# PLIS_POWER.net
KiCad netlist of a schematic drawn in Altium Designer
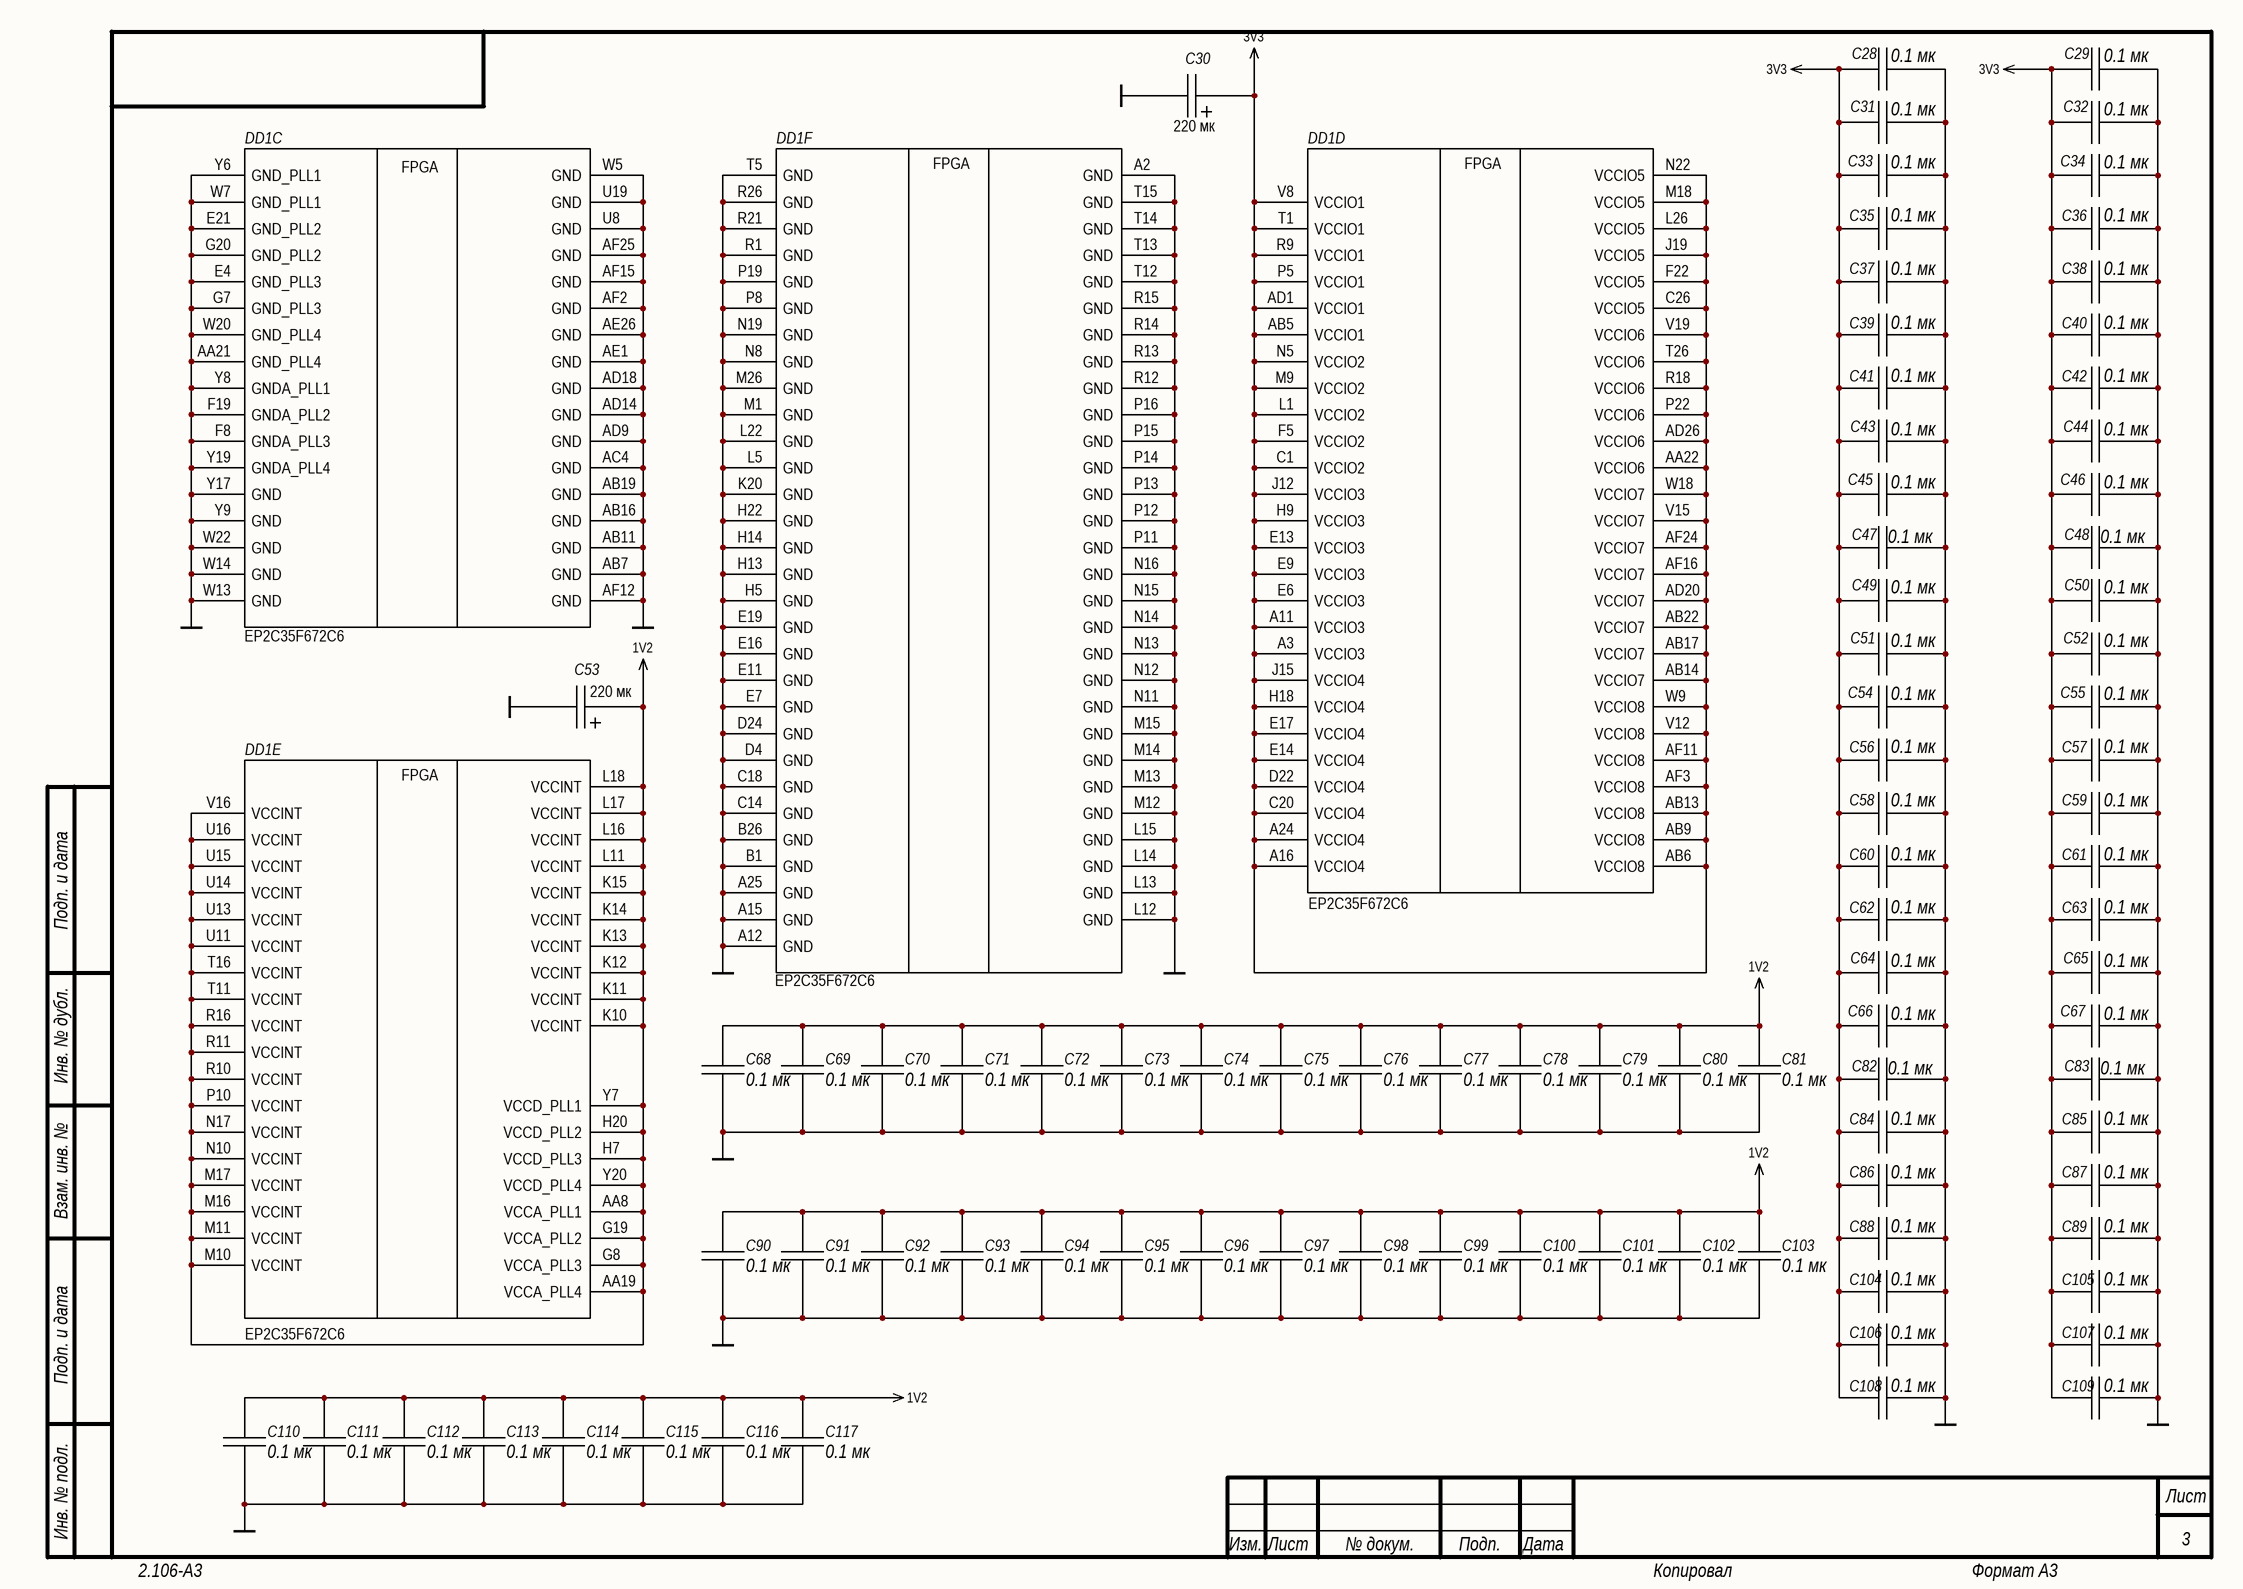
[diagram p0: PLIS_POWER.SchDoc]

(export (version "E")
  (design (tool "Eeschema 10.0.6"))
  (components
    (comp (ref "C28") (value "0.1 мк") (libsource (lib "Schlib1") (part "C")))
    (comp (ref "C29") (value "0.1 мк") (libsource (lib "Schlib1") (part "C")))
    (comp (ref "C30") (value "~") (libsource (lib "Schlib1") (part "C_POL")))
    (comp (ref "C31") (value "0.1 мк") (libsource (lib "Schlib1") (part "C")))
    (comp (ref "C32") (value "0.1 мк") (libsource (lib "Schlib1") (part "C")))
    (comp (ref "C33") (value "0.1 мк") (libsource (lib "Schlib1") (part "C")))
    (comp (ref "C34") (value "0.1 мк") (libsource (lib "Schlib1") (part "C")))
    (comp (ref "C35") (value "0.1 мк") (libsource (lib "Schlib1") (part "C")))
    (comp (ref "C36") (value "0.1 мк") (libsource (lib "Schlib1") (part "C")))
    (comp (ref "C37") (value "0.1 мк") (libsource (lib "Schlib1") (part "C")))
    (comp (ref "C38") (value "0.1 мк") (libsource (lib "Schlib1") (part "C")))
    (comp (ref "C39") (value "0.1 мк") (libsource (lib "Schlib1") (part "C")))
    (comp (ref "C40") (value "0.1 мк") (libsource (lib "Schlib1") (part "C")))
    (comp (ref "C41") (value "0.1 мк") (libsource (lib "Schlib1") (part "C")))
    (comp (ref "C42") (value "0.1 мк") (libsource (lib "Schlib1") (part "C")))
    (comp (ref "C43") (value "0.1 мк") (libsource (lib "Schlib1") (part "C")))
    (comp (ref "C44") (value "0.1 мк") (libsource (lib "Schlib1") (part "C")))
    (comp (ref "C45") (value "0.1 мк") (libsource (lib "Schlib1") (part "C")))
    (comp (ref "C46") (value "0.1 мк") (libsource (lib "Schlib1") (part "C")))
    (comp (ref "C47") (value "0.1 мк") (libsource (lib "Schlib1") (part "C")))
    (comp (ref "C48") (value "0.1 мк") (libsource (lib "Schlib1") (part "C")))
    (comp (ref "C49") (value "0.1 мк") (libsource (lib "Schlib1") (part "C")))
    (comp (ref "C50") (value "0.1 мк") (libsource (lib "Schlib1") (part "C")))
    (comp (ref "C51") (value "0.1 мк") (libsource (lib "Schlib1") (part "C")))
    (comp (ref "C52") (value "0.1 мк") (libsource (lib "Schlib1") (part "C")))
    (comp (ref "C53") (value "~") (libsource (lib "Schlib1") (part "C_POL")))
    (comp (ref "C54") (value "0.1 мк") (libsource (lib "Schlib1") (part "C")))
    (comp (ref "C55") (value "0.1 мк") (libsource (lib "Schlib1") (part "C")))
    (comp (ref "C56") (value "0.1 мк") (libsource (lib "Schlib1") (part "C")))
    (comp (ref "C57") (value "0.1 мк") (libsource (lib "Schlib1") (part "C")))
    (comp (ref "C58") (value "0.1 мк") (libsource (lib "Schlib1") (part "C")))
    (comp (ref "C59") (value "0.1 мк") (libsource (lib "Schlib1") (part "C")))
    (comp (ref "C60") (value "0.1 мк") (libsource (lib "Schlib1") (part "C")))
    (comp (ref "C61") (value "0.1 мк") (libsource (lib "Schlib1") (part "C")))
    (comp (ref "C62") (value "0.1 мк") (libsource (lib "Schlib1") (part "C")))
    (comp (ref "C63") (value "0.1 мк") (libsource (lib "Schlib1") (part "C")))
    (comp (ref "C64") (value "0.1 мк") (libsource (lib "Schlib1") (part "C")))
    (comp (ref "C65") (value "0.1 мк") (libsource (lib "Schlib1") (part "C")))
    (comp (ref "C66") (value "0.1 мк") (libsource (lib "Schlib1") (part "C")))
    (comp (ref "C67") (value "0.1 мк") (libsource (lib "Schlib1") (part "C")))
    (comp (ref "C68") (value "0.1 мк") (libsource (lib "Schlib1") (part "C")))
    (comp (ref "C69") (value "0.1 мк") (libsource (lib "Schlib1") (part "C")))
    (comp (ref "C70") (value "0.1 мк") (libsource (lib "Schlib1") (part "C")))
    (comp (ref "C71") (value "0.1 мк") (libsource (lib "Schlib1") (part "C")))
    (comp (ref "C72") (value "0.1 мк") (libsource (lib "Schlib1") (part "C")))
    (comp (ref "C73") (value "0.1 мк") (libsource (lib "Schlib1") (part "C")))
    (comp (ref "C74") (value "0.1 мк") (libsource (lib "Schlib1") (part "C")))
    (comp (ref "C75") (value "0.1 мк") (libsource (lib "Schlib1") (part "C")))
    (comp (ref "C76") (value "0.1 мк") (libsource (lib "Schlib1") (part "C")))
    (comp (ref "C77") (value "0.1 мк") (libsource (lib "Schlib1") (part "C")))
    (comp (ref "C78") (value "0.1 мк") (libsource (lib "Schlib1") (part "C")))
    (comp (ref "C79") (value "0.1 мк") (libsource (lib "Schlib1") (part "C")))
    (comp (ref "C80") (value "0.1 мк") (libsource (lib "Schlib1") (part "C")))
    (comp (ref "C81") (value "0.1 мк") (libsource (lib "Schlib1") (part "C")))
    (comp (ref "C82") (value "0.1 мк") (libsource (lib "Schlib1") (part "C")))
    (comp (ref "C83") (value "0.1 мк") (libsource (lib "Schlib1") (part "C")))
    (comp (ref "C84") (value "0.1 мк") (libsource (lib "Schlib1") (part "C")))
    (comp (ref "C85") (value "0.1 мк") (libsource (lib "Schlib1") (part "C")))
    (comp (ref "C86") (value "0.1 мк") (libsource (lib "Schlib1") (part "C")))
    (comp (ref "C87") (value "0.1 мк") (libsource (lib "Schlib1") (part "C")))
    (comp (ref "C88") (value "0.1 мк") (libsource (lib "Schlib1") (part "C")))
    (comp (ref "C89") (value "0.1 мк") (libsource (lib "Schlib1") (part "C")))
    (comp (ref "C90") (value "0.1 мк") (libsource (lib "Schlib1") (part "C")))
    (comp (ref "C91") (value "0.1 мк") (libsource (lib "Schlib1") (part "C")))
    (comp (ref "C92") (value "0.1 мк") (libsource (lib "Schlib1") (part "C")))
    (comp (ref "C93") (value "0.1 мк") (libsource (lib "Schlib1") (part "C")))
    (comp (ref "C94") (value "0.1 мк") (libsource (lib "Schlib1") (part "C")))
    (comp (ref "C95") (value "0.1 мк") (libsource (lib "Schlib1") (part "C")))
    (comp (ref "C96") (value "0.1 мк") (libsource (lib "Schlib1") (part "C")))
    (comp (ref "C97") (value "0.1 мк") (libsource (lib "Schlib1") (part "C")))
    (comp (ref "C98") (value "0.1 мк") (libsource (lib "Schlib1") (part "C")))
    (comp (ref "C99") (value "0.1 мк") (libsource (lib "Schlib1") (part "C")))
    (comp (ref "C100") (value "0.1 мк") (libsource (lib "Schlib1") (part "C")))
    (comp (ref "C101") (value "0.1 мк") (libsource (lib "Schlib1") (part "C")))
    (comp (ref "C102") (value "0.1 мк") (libsource (lib "Schlib1") (part "C")))
    (comp (ref "C103") (value "0.1 мк") (libsource (lib "Schlib1") (part "C")))
    (comp (ref "C104") (value "0.1 мк") (libsource (lib "Schlib1") (part "C")))
    (comp (ref "C105") (value "0.1 мк") (libsource (lib "Schlib1") (part "C")))
    (comp (ref "C106") (value "0.1 мк") (libsource (lib "Schlib1") (part "C")))
    (comp (ref "C107") (value "0.1 мк") (libsource (lib "Schlib1") (part "C")))
    (comp (ref "C108") (value "0.1 мк") (libsource (lib "Schlib1") (part "C")))
    (comp (ref "C109") (value "0.1 мк") (libsource (lib "Schlib1") (part "C")))
    (comp (ref "C110") (value "0.1 мк") (libsource (lib "Schlib1") (part "C")))
    (comp (ref "C111") (value "0.1 мк") (libsource (lib "Schlib1") (part "C")))
    (comp (ref "C112") (value "0.1 мк") (libsource (lib "Schlib1") (part "C")))
    (comp (ref "C113") (value "0.1 мк") (libsource (lib "Schlib1") (part "C")))
    (comp (ref "C114") (value "0.1 мк") (libsource (lib "Schlib1") (part "C")))
    (comp (ref "C115") (value "0.1 мк") (libsource (lib "Schlib1") (part "C")))
    (comp (ref "C116") (value "0.1 мк") (libsource (lib "Schlib1") (part "C")))
    (comp (ref "C117") (value "0.1 мк") (libsource (lib "Schlib1") (part "C")))
    (comp (ref "DD1") (value "EP2C35F672C6") (libsource (lib "Schlib1") (part "PLIS")))
  )
  (nets
    (net (code "1") (name "1V2") (class "Default")
      (node (ref "C100") (pin "1") (pintype "passive"))
      (node (ref "C101") (pin "1") (pintype "passive"))
      (node (ref "C102") (pin "1") (pintype "passive"))
      (node (ref "C103") (pin "1") (pintype "passive"))
      (node (ref "C110") (pin "1") (pintype "passive"))
      (node (ref "C111") (pin "1") (pintype "passive"))
      (node (ref "C112") (pin "1") (pintype "passive"))
      (node (ref "C113") (pin "1") (pintype "passive"))
      (node (ref "C114") (pin "1") (pintype "passive"))
      (node (ref "C115") (pin "1") (pintype "passive"))
      (node (ref "C116") (pin "1") (pintype "passive"))
      (node (ref "C117") (pin "1") (pintype "passive"))
      (node (ref "C53") (pin "2") (pintype "passive"))
      (node (ref "C68") (pin "1") (pintype "passive"))
      (node (ref "C69") (pin "1") (pintype "passive"))
      (node (ref "C70") (pin "1") (pintype "passive"))
      (node (ref "C71") (pin "1") (pintype "passive"))
      (node (ref "C72") (pin "1") (pintype "passive"))
      (node (ref "C73") (pin "1") (pintype "passive"))
      (node (ref "C74") (pin "1") (pintype "passive"))
      (node (ref "C75") (pin "1") (pintype "passive"))
      (node (ref "C76") (pin "1") (pintype "passive"))
      (node (ref "C77") (pin "1") (pintype "passive"))
      (node (ref "C78") (pin "1") (pintype "passive"))
      (node (ref "C79") (pin "1") (pintype "passive"))
      (node (ref "C80") (pin "1") (pintype "passive"))
      (node (ref "C81") (pin "1") (pintype "passive"))
      (node (ref "C90") (pin "1") (pintype "passive"))
      (node (ref "C91") (pin "1") (pintype "passive"))
      (node (ref "C92") (pin "1") (pintype "passive"))
      (node (ref "C93") (pin "1") (pintype "passive"))
      (node (ref "C94") (pin "1") (pintype "passive"))
      (node (ref "C95") (pin "1") (pintype "passive"))
      (node (ref "C96") (pin "1") (pintype "passive"))
      (node (ref "C97") (pin "1") (pintype "passive"))
      (node (ref "C98") (pin "1") (pintype "passive"))
      (node (ref "C99") (pin "1") (pintype "passive"))
      (node (ref "DD1") (pin "AA19") (pinfunction "VCCA_PLL4_AA19") (pintype "passive"))
      (node (ref "DD1") (pin "AA8") (pinfunction "VCCA_PLL1_AA8") (pintype "passive"))
      (node (ref "DD1") (pin "G19") (pinfunction "VCCA_PLL2_G19") (pintype "passive"))
      (node (ref "DD1") (pin "G8") (pinfunction "VCCA_PLL3_G8") (pintype "passive"))
      (node (ref "DD1") (pin "H20") (pinfunction "VCCD_PLL2_H20") (pintype "passive"))
      (node (ref "DD1") (pin "H7") (pinfunction "VCCD_PLL3_H7") (pintype "passive"))
      (node (ref "DD1") (pin "K10") (pinfunction "VCCINT_K10") (pintype "passive"))
      (node (ref "DD1") (pin "K11") (pinfunction "VCCINT_K11") (pintype "passive"))
      (node (ref "DD1") (pin "K12") (pinfunction "VCCINT_K12") (pintype "passive"))
      (node (ref "DD1") (pin "K13") (pinfunction "VCCINT_K13") (pintype "passive"))
      (node (ref "DD1") (pin "K14") (pinfunction "VCCINT_K14") (pintype "passive"))
      (node (ref "DD1") (pin "K15") (pinfunction "VCCINT_K15") (pintype "passive"))
      (node (ref "DD1") (pin "L11") (pinfunction "VCCINT_L11") (pintype "passive"))
      (node (ref "DD1") (pin "L16") (pinfunction "VCCINT_L16") (pintype "passive"))
      (node (ref "DD1") (pin "L17") (pinfunction "VCCINT_L17") (pintype "passive"))
      (node (ref "DD1") (pin "L18") (pinfunction "VCCINT_L18") (pintype "passive"))
      (node (ref "DD1") (pin "M10") (pinfunction "VCCINT_M10") (pintype "passive"))
      (node (ref "DD1") (pin "M11") (pinfunction "VCCINT_M11") (pintype "passive"))
      (node (ref "DD1") (pin "M16") (pinfunction "VCCINT_M16") (pintype "passive"))
      (node (ref "DD1") (pin "M17") (pinfunction "VCCINT_M17") (pintype "passive"))
      (node (ref "DD1") (pin "N10") (pinfunction "VCCINT_N10") (pintype "passive"))
      (node (ref "DD1") (pin "N17") (pinfunction "VCCINT_N17") (pintype "passive"))
      (node (ref "DD1") (pin "P10") (pinfunction "VCCINT_P10") (pintype "passive"))
      (node (ref "DD1") (pin "R10") (pinfunction "VCCINT_R10") (pintype "passive"))
      (node (ref "DD1") (pin "R11") (pinfunction "VCCINT_R11") (pintype "passive"))
      (node (ref "DD1") (pin "R16") (pinfunction "VCCINT_R16") (pintype "passive"))
      (node (ref "DD1") (pin "T11") (pinfunction "VCCINT_T11") (pintype "passive"))
      (node (ref "DD1") (pin "T16") (pinfunction "VCCINT_T16") (pintype "passive"))
      (node (ref "DD1") (pin "U11") (pinfunction "VCCINT_U11") (pintype "passive"))
      (node (ref "DD1") (pin "U13") (pinfunction "VCCINT_U13") (pintype "passive"))
      (node (ref "DD1") (pin "U14") (pinfunction "VCCINT_U14") (pintype "passive"))
      (node (ref "DD1") (pin "U15") (pinfunction "VCCINT_U15") (pintype "passive"))
      (node (ref "DD1") (pin "U16") (pinfunction "VCCINT_U16") (pintype "passive"))
      (node (ref "DD1") (pin "V16") (pinfunction "VCCINT_V16") (pintype "passive"))
      (node (ref "DD1") (pin "Y20") (pinfunction "VCCD_PLL4_Y20") (pintype "passive"))
      (node (ref "DD1") (pin "Y7") (pinfunction "VCCD_PLL1_Y7") (pintype "passive"))
    )
    (net (code "2") (name "3V3") (class "Default")
      (node (ref "C104") (pin "1") (pintype "passive"))
      (node (ref "C105") (pin "1") (pintype "passive"))
      (node (ref "C106") (pin "1") (pintype "passive"))
      (node (ref "C107") (pin "1") (pintype "passive"))
      (node (ref "C108") (pin "1") (pintype "passive"))
      (node (ref "C109") (pin "1") (pintype "passive"))
      (node (ref "C28") (pin "1") (pintype "passive"))
      (node (ref "C29") (pin "1") (pintype "passive"))
      (node (ref "C30") (pin "2") (pintype "passive"))
      (node (ref "C31") (pin "1") (pintype "passive"))
      (node (ref "C32") (pin "1") (pintype "passive"))
      (node (ref "C33") (pin "1") (pintype "passive"))
      (node (ref "C34") (pin "1") (pintype "passive"))
      (node (ref "C35") (pin "1") (pintype "passive"))
      (node (ref "C36") (pin "1") (pintype "passive"))
      (node (ref "C37") (pin "1") (pintype "passive"))
      (node (ref "C38") (pin "1") (pintype "passive"))
      (node (ref "C39") (pin "1") (pintype "passive"))
      (node (ref "C40") (pin "1") (pintype "passive"))
      (node (ref "C41") (pin "1") (pintype "passive"))
      (node (ref "C42") (pin "1") (pintype "passive"))
      (node (ref "C43") (pin "1") (pintype "passive"))
      (node (ref "C44") (pin "1") (pintype "passive"))
      (node (ref "C45") (pin "1") (pintype "passive"))
      (node (ref "C46") (pin "1") (pintype "passive"))
      (node (ref "C47") (pin "1") (pintype "passive"))
      (node (ref "C48") (pin "1") (pintype "passive"))
      (node (ref "C49") (pin "1") (pintype "passive"))
      (node (ref "C50") (pin "1") (pintype "passive"))
      (node (ref "C51") (pin "1") (pintype "passive"))
      (node (ref "C52") (pin "1") (pintype "passive"))
      (node (ref "C54") (pin "1") (pintype "passive"))
      (node (ref "C55") (pin "1") (pintype "passive"))
      (node (ref "C56") (pin "1") (pintype "passive"))
      (node (ref "C57") (pin "1") (pintype "passive"))
      (node (ref "C58") (pin "1") (pintype "passive"))
      (node (ref "C59") (pin "1") (pintype "passive"))
      (node (ref "C60") (pin "1") (pintype "passive"))
      (node (ref "C61") (pin "1") (pintype "passive"))
      (node (ref "C62") (pin "1") (pintype "passive"))
      (node (ref "C63") (pin "1") (pintype "passive"))
      (node (ref "C64") (pin "1") (pintype "passive"))
      (node (ref "C65") (pin "1") (pintype "passive"))
      (node (ref "C66") (pin "1") (pintype "passive"))
      (node (ref "C67") (pin "1") (pintype "passive"))
      (node (ref "C82") (pin "1") (pintype "passive"))
      (node (ref "C83") (pin "1") (pintype "passive"))
      (node (ref "C84") (pin "1") (pintype "passive"))
      (node (ref "C85") (pin "1") (pintype "passive"))
      (node (ref "C86") (pin "1") (pintype "passive"))
      (node (ref "C87") (pin "1") (pintype "passive"))
      (node (ref "C88") (pin "1") (pintype "passive"))
      (node (ref "C89") (pin "1") (pintype "passive"))
      (node (ref "DD1") (pin "A11") (pinfunction "VCCIO3_A11") (pintype "passive"))
      (node (ref "DD1") (pin "A16") (pinfunction "VCCIO4_A16") (pintype "passive"))
      (node (ref "DD1") (pin "A24") (pinfunction "VCCIO4_A24") (pintype "passive"))
      (node (ref "DD1") (pin "A3") (pinfunction "VCCIO3_A3") (pintype "passive"))
      (node (ref "DD1") (pin "AA22") (pinfunction "VCCIO6_AA22") (pintype "passive"))
      (node (ref "DD1") (pin "AB13") (pinfunction "VCCIO8_AB13") (pintype "passive"))
      (node (ref "DD1") (pin "AB14") (pinfunction "VCCIO7_AB14") (pintype "passive"))
      (node (ref "DD1") (pin "AB17") (pinfunction "VCCIO7_AB17") (pintype "passive"))
      (node (ref "DD1") (pin "AB22") (pinfunction "VCCIO7_AB22") (pintype "passive"))
      (node (ref "DD1") (pin "AB5") (pinfunction "VCCIO1_AB5") (pintype "passive"))
      (node (ref "DD1") (pin "AB6") (pinfunction "VCCIO8_AB6") (pintype "passive"))
      (node (ref "DD1") (pin "AB9") (pinfunction "VCCIO8_AB9") (pintype "passive"))
      (node (ref "DD1") (pin "AD1") (pinfunction "VCCIO1_AD1") (pintype "passive"))
      (node (ref "DD1") (pin "AD20") (pinfunction "VCCIO7_AD20") (pintype "passive"))
      (node (ref "DD1") (pin "AD26") (pinfunction "VCCIO6_AD26") (pintype "passive"))
      (node (ref "DD1") (pin "AF11") (pinfunction "VCCIO8_AF11") (pintype "passive"))
      (node (ref "DD1") (pin "AF16") (pinfunction "VCCIO7_AF16") (pintype "passive"))
      (node (ref "DD1") (pin "AF24") (pinfunction "VCCIO7_AF24") (pintype "passive"))
      (node (ref "DD1") (pin "AF3") (pinfunction "VCCIO8_AF3") (pintype "passive"))
      (node (ref "DD1") (pin "C1") (pinfunction "VCCIO2_C1") (pintype "passive"))
      (node (ref "DD1") (pin "C20") (pinfunction "VCCIO4_C20") (pintype "passive"))
      (node (ref "DD1") (pin "C26") (pinfunction "VCCIO5_C26") (pintype "passive"))
      (node (ref "DD1") (pin "D22") (pinfunction "VCCIO4_D22") (pintype "passive"))
      (node (ref "DD1") (pin "E13") (pinfunction "VCCIO3_E13") (pintype "passive"))
      (node (ref "DD1") (pin "E14") (pinfunction "VCCIO4_E14") (pintype "passive"))
      (node (ref "DD1") (pin "E17") (pinfunction "VCCIO4_E17") (pintype "passive"))
      (node (ref "DD1") (pin "E6") (pinfunction "VCCIO3_E6") (pintype "passive"))
      (node (ref "DD1") (pin "E9") (pinfunction "VCCIO3_E9") (pintype "passive"))
      (node (ref "DD1") (pin "F22") (pinfunction "VCCIO5_F22") (pintype "passive"))
      (node (ref "DD1") (pin "F5") (pinfunction "VCCIO2_F5") (pintype "passive"))
      (node (ref "DD1") (pin "H18") (pinfunction "VCCIO4_H18") (pintype "passive"))
      (node (ref "DD1") (pin "H9") (pinfunction "VCCIO3_H9") (pintype "passive"))
      (node (ref "DD1") (pin "J12") (pinfunction "VCCIO3_J12") (pintype "passive"))
      (node (ref "DD1") (pin "J15") (pinfunction "VCCIO4_J15") (pintype "passive"))
      (node (ref "DD1") (pin "J19") (pinfunction "VCCIO5_J19") (pintype "passive"))
      (node (ref "DD1") (pin "L1") (pinfunction "VCCIO2_L1") (pintype "passive"))
      (node (ref "DD1") (pin "L26") (pinfunction "VCCIO5_L26") (pintype "passive"))
      (node (ref "DD1") (pin "M18") (pinfunction "VCCIO5_M18") (pintype "passive"))
      (node (ref "DD1") (pin "M9") (pinfunction "VCCIO2_M9") (pintype "passive"))
      (node (ref "DD1") (pin "N22") (pinfunction "VCCIO5_N22") (pintype "passive"))
      (node (ref "DD1") (pin "N5") (pinfunction "VCCIO2_N5") (pintype "passive"))
      (node (ref "DD1") (pin "P22") (pinfunction "VCCIO6_P22") (pintype "passive"))
      (node (ref "DD1") (pin "P5") (pinfunction "VCCIO1_P5") (pintype "passive"))
      (node (ref "DD1") (pin "R18") (pinfunction "VCCIO6_R18") (pintype "passive"))
      (node (ref "DD1") (pin "R9") (pinfunction "VCCIO1_R9") (pintype "passive"))
      (node (ref "DD1") (pin "T1") (pinfunction "VCCIO1_T1") (pintype "passive"))
      (node (ref "DD1") (pin "T26") (pinfunction "VCCIO6_T26") (pintype "passive"))
      (node (ref "DD1") (pin "V12") (pinfunction "VCCIO8_V12") (pintype "passive"))
      (node (ref "DD1") (pin "V15") (pinfunction "VCCIO7_V15") (pintype "passive"))
      (node (ref "DD1") (pin "V19") (pinfunction "VCCIO6_V19") (pintype "passive"))
      (node (ref "DD1") (pin "V8") (pinfunction "VCCIO1_V8") (pintype "passive"))
      (node (ref "DD1") (pin "W18") (pinfunction "VCCIO7_W18") (pintype "passive"))
      (node (ref "DD1") (pin "W9") (pinfunction "VCCIO8_W9") (pintype "passive"))
    )
    (net (code "3") (name "GND") (class "Default")
      (node (ref "C100") (pin "2") (pintype "passive"))
      (node (ref "C101") (pin "2") (pintype "passive"))
      (node (ref "C102") (pin "2") (pintype "passive"))
      (node (ref "C103") (pin "2") (pintype "passive"))
      (node (ref "C104") (pin "2") (pintype "passive"))
      (node (ref "C105") (pin "2") (pintype "passive"))
      (node (ref "C106") (pin "2") (pintype "passive"))
      (node (ref "C107") (pin "2") (pintype "passive"))
      (node (ref "C108") (pin "2") (pintype "passive"))
      (node (ref "C109") (pin "2") (pintype "passive"))
      (node (ref "C110") (pin "2") (pintype "passive"))
      (node (ref "C111") (pin "2") (pintype "passive"))
      (node (ref "C112") (pin "2") (pintype "passive"))
      (node (ref "C113") (pin "2") (pintype "passive"))
      (node (ref "C114") (pin "2") (pintype "passive"))
      (node (ref "C115") (pin "2") (pintype "passive"))
      (node (ref "C116") (pin "2") (pintype "passive"))
      (node (ref "C117") (pin "2") (pintype "passive"))
      (node (ref "C28") (pin "2") (pintype "passive"))
      (node (ref "C29") (pin "2") (pintype "passive"))
      (node (ref "C30") (pin "1") (pintype "passive"))
      (node (ref "C31") (pin "2") (pintype "passive"))
      (node (ref "C32") (pin "2") (pintype "passive"))
      (node (ref "C33") (pin "2") (pintype "passive"))
      (node (ref "C34") (pin "2") (pintype "passive"))
      (node (ref "C35") (pin "2") (pintype "passive"))
      (node (ref "C36") (pin "2") (pintype "passive"))
      (node (ref "C37") (pin "2") (pintype "passive"))
      (node (ref "C38") (pin "2") (pintype "passive"))
      (node (ref "C39") (pin "2") (pintype "passive"))
      (node (ref "C40") (pin "2") (pintype "passive"))
      (node (ref "C41") (pin "2") (pintype "passive"))
      (node (ref "C42") (pin "2") (pintype "passive"))
      (node (ref "C43") (pin "2") (pintype "passive"))
      (node (ref "C44") (pin "2") (pintype "passive"))
      (node (ref "C45") (pin "2") (pintype "passive"))
      (node (ref "C46") (pin "2") (pintype "passive"))
      (node (ref "C47") (pin "2") (pintype "passive"))
      (node (ref "C48") (pin "2") (pintype "passive"))
      (node (ref "C49") (pin "2") (pintype "passive"))
      (node (ref "C50") (pin "2") (pintype "passive"))
      (node (ref "C51") (pin "2") (pintype "passive"))
      (node (ref "C52") (pin "2") (pintype "passive"))
      (node (ref "C53") (pin "1") (pintype "passive"))
      (node (ref "C54") (pin "2") (pintype "passive"))
      (node (ref "C55") (pin "2") (pintype "passive"))
      (node (ref "C56") (pin "2") (pintype "passive"))
      (node (ref "C57") (pin "2") (pintype "passive"))
      (node (ref "C58") (pin "2") (pintype "passive"))
      (node (ref "C59") (pin "2") (pintype "passive"))
      (node (ref "C60") (pin "2") (pintype "passive"))
      (node (ref "C61") (pin "2") (pintype "passive"))
      (node (ref "C62") (pin "2") (pintype "passive"))
      (node (ref "C63") (pin "2") (pintype "passive"))
      (node (ref "C64") (pin "2") (pintype "passive"))
      (node (ref "C65") (pin "2") (pintype "passive"))
      (node (ref "C66") (pin "2") (pintype "passive"))
      (node (ref "C67") (pin "2") (pintype "passive"))
      (node (ref "C68") (pin "2") (pintype "passive"))
      (node (ref "C69") (pin "2") (pintype "passive"))
      (node (ref "C70") (pin "2") (pintype "passive"))
      (node (ref "C71") (pin "2") (pintype "passive"))
      (node (ref "C72") (pin "2") (pintype "passive"))
      (node (ref "C73") (pin "2") (pintype "passive"))
      (node (ref "C74") (pin "2") (pintype "passive"))
      (node (ref "C75") (pin "2") (pintype "passive"))
      (node (ref "C76") (pin "2") (pintype "passive"))
      (node (ref "C77") (pin "2") (pintype "passive"))
      (node (ref "C78") (pin "2") (pintype "passive"))
      (node (ref "C79") (pin "2") (pintype "passive"))
      (node (ref "C80") (pin "2") (pintype "passive"))
      (node (ref "C81") (pin "2") (pintype "passive"))
      (node (ref "C82") (pin "2") (pintype "passive"))
      (node (ref "C83") (pin "2") (pintype "passive"))
      (node (ref "C84") (pin "2") (pintype "passive"))
      (node (ref "C85") (pin "2") (pintype "passive"))
      (node (ref "C86") (pin "2") (pintype "passive"))
      (node (ref "C87") (pin "2") (pintype "passive"))
      (node (ref "C88") (pin "2") (pintype "passive"))
      (node (ref "C89") (pin "2") (pintype "passive"))
      (node (ref "C90") (pin "2") (pintype "passive"))
      (node (ref "C91") (pin "2") (pintype "passive"))
      (node (ref "C92") (pin "2") (pintype "passive"))
      (node (ref "C93") (pin "2") (pintype "passive"))
      (node (ref "C94") (pin "2") (pintype "passive"))
      (node (ref "C95") (pin "2") (pintype "passive"))
      (node (ref "C96") (pin "2") (pintype "passive"))
      (node (ref "C97") (pin "2") (pintype "passive"))
      (node (ref "C98") (pin "2") (pintype "passive"))
      (node (ref "C99") (pin "2") (pintype "passive"))
      (node (ref "DD1") (pin "A12") (pinfunction "GND_A12") (pintype "passive"))
      (node (ref "DD1") (pin "A15") (pinfunction "GND_A15") (pintype "passive"))
      (node (ref "DD1") (pin "A2") (pinfunction "GND_A2") (pintype "passive"))
      (node (ref "DD1") (pin "A25") (pinfunction "GND_A25") (pintype "passive"))
      (node (ref "DD1") (pin "AA21") (pinfunction "GND_PLL4_AA21") (pintype "passive"))
      (node (ref "DD1") (pin "AB11") (pinfunction "GND_AB11") (pintype "passive"))
      (node (ref "DD1") (pin "AB16") (pinfunction "GND_AB16") (pintype "passive"))
      (node (ref "DD1") (pin "AB19") (pinfunction "GND_AB19") (pintype "passive"))
      (node (ref "DD1") (pin "AB7") (pinfunction "GND_AB7") (pintype "passive"))
      (node (ref "DD1") (pin "AC4") (pinfunction "GND_AC4") (pintype "passive"))
      (node (ref "DD1") (pin "AD14") (pinfunction "GND_AD14") (pintype "passive"))
      (node (ref "DD1") (pin "AD18") (pinfunction "GND_AD18") (pintype "passive"))
      (node (ref "DD1") (pin "AD9") (pinfunction "GND_AD9") (pintype "passive"))
      (node (ref "DD1") (pin "AE1") (pinfunction "GND_AE1") (pintype "passive"))
      (node (ref "DD1") (pin "AE26") (pinfunction "GND_AE26") (pintype "passive"))
      (node (ref "DD1") (pin "AF12") (pinfunction "GND_AF12") (pintype "passive"))
      (node (ref "DD1") (pin "AF15") (pinfunction "GND_AF15") (pintype "passive"))
      (node (ref "DD1") (pin "AF2") (pinfunction "GND_AF2") (pintype "passive"))
      (node (ref "DD1") (pin "AF25") (pinfunction "GND_AF25") (pintype "passive"))
      (node (ref "DD1") (pin "B1") (pinfunction "GND_B1") (pintype "passive"))
      (node (ref "DD1") (pin "B26") (pinfunction "GND_B26") (pintype "passive"))
      (node (ref "DD1") (pin "C14") (pinfunction "GND_C14") (pintype "passive"))
      (node (ref "DD1") (pin "C18") (pinfunction "GND_C18") (pintype "passive"))
      (node (ref "DD1") (pin "D24") (pinfunction "GND_D24") (pintype "passive"))
      (node (ref "DD1") (pin "D4") (pinfunction "GND_D4") (pintype "passive"))
      (node (ref "DD1") (pin "E11") (pinfunction "GND_E11") (pintype "passive"))
      (node (ref "DD1") (pin "E16") (pinfunction "GND_E16") (pintype "passive"))
      (node (ref "DD1") (pin "E19") (pinfunction "GND_E19") (pintype "passive"))
      (node (ref "DD1") (pin "E21") (pinfunction "GND_PLL2_E21") (pintype "passive"))
      (node (ref "DD1") (pin "E4") (pinfunction "GND_PLL3_E4") (pintype "passive"))
      (node (ref "DD1") (pin "E7") (pinfunction "GND_E7") (pintype "passive"))
      (node (ref "DD1") (pin "F19") (pinfunction "GNDA_PLL2_F19") (pintype "passive"))
      (node (ref "DD1") (pin "F8") (pinfunction "GNDA_PLL3_F8") (pintype "passive"))
      (node (ref "DD1") (pin "G20") (pinfunction "GND_PLL2_G20") (pintype "passive"))
      (node (ref "DD1") (pin "G7") (pinfunction "GND_PLL3_G7") (pintype "passive"))
      (node (ref "DD1") (pin "H13") (pinfunction "GND_H13") (pintype "passive"))
      (node (ref "DD1") (pin "H14") (pinfunction "GND_H14") (pintype "passive"))
      (node (ref "DD1") (pin "H22") (pinfunction "GND_H22") (pintype "passive"))
      (node (ref "DD1") (pin "H5") (pinfunction "GND_H5") (pintype "passive"))
      (node (ref "DD1") (pin "K20") (pinfunction "GND_K20") (pintype "passive"))
      (node (ref "DD1") (pin "L12") (pinfunction "GND_L12") (pintype "passive"))
      (node (ref "DD1") (pin "L13") (pinfunction "GND_L13") (pintype "passive"))
      (node (ref "DD1") (pin "L14") (pinfunction "GND_L14") (pintype "passive"))
      (node (ref "DD1") (pin "L15") (pinfunction "GND_L15") (pintype "passive"))
      (node (ref "DD1") (pin "L22") (pinfunction "GND_L22") (pintype "passive"))
      (node (ref "DD1") (pin "L5") (pinfunction "GND_L5") (pintype "passive"))
      (node (ref "DD1") (pin "M1") (pinfunction "GND_M1") (pintype "passive"))
      (node (ref "DD1") (pin "M12") (pinfunction "GND_M12") (pintype "passive"))
      (node (ref "DD1") (pin "M13") (pinfunction "GND_M13") (pintype "passive"))
      (node (ref "DD1") (pin "M14") (pinfunction "GND_M14") (pintype "passive"))
      (node (ref "DD1") (pin "M15") (pinfunction "GND_M15") (pintype "passive"))
      (node (ref "DD1") (pin "M26") (pinfunction "GND_M26") (pintype "passive"))
      (node (ref "DD1") (pin "N11") (pinfunction "GND_N11") (pintype "passive"))
      (node (ref "DD1") (pin "N12") (pinfunction "GND_N12") (pintype "passive"))
      (node (ref "DD1") (pin "N13") (pinfunction "GND_N13") (pintype "passive"))
      (node (ref "DD1") (pin "N14") (pinfunction "GND_N14") (pintype "passive"))
      (node (ref "DD1") (pin "N15") (pinfunction "GND_N15") (pintype "passive"))
      (node (ref "DD1") (pin "N16") (pinfunction "GND_N16") (pintype "passive"))
      (node (ref "DD1") (pin "N19") (pinfunction "GND_N19") (pintype "passive"))
      (node (ref "DD1") (pin "N8") (pinfunction "GND_N8") (pintype "passive"))
      (node (ref "DD1") (pin "P11") (pinfunction "GND_P11") (pintype "passive"))
      (node (ref "DD1") (pin "P12") (pinfunction "GND_P12") (pintype "passive"))
      (node (ref "DD1") (pin "P13") (pinfunction "GND_P13") (pintype "passive"))
      (node (ref "DD1") (pin "P14") (pinfunction "GND_P14") (pintype "passive"))
      (node (ref "DD1") (pin "P15") (pinfunction "GND_P15") (pintype "passive"))
      (node (ref "DD1") (pin "P16") (pinfunction "GND_P16") (pintype "passive"))
      (node (ref "DD1") (pin "P19") (pinfunction "GND_P19") (pintype "passive"))
      (node (ref "DD1") (pin "P8") (pinfunction "GND_P8") (pintype "passive"))
      (node (ref "DD1") (pin "R1") (pinfunction "GND_R1") (pintype "passive"))
      (node (ref "DD1") (pin "R12") (pinfunction "GND_R12") (pintype "passive"))
      (node (ref "DD1") (pin "R13") (pinfunction "GND_R13") (pintype "passive"))
      (node (ref "DD1") (pin "R14") (pinfunction "GND_R14") (pintype "passive"))
      (node (ref "DD1") (pin "R15") (pinfunction "GND_R15") (pintype "passive"))
      (node (ref "DD1") (pin "R21") (pinfunction "GND_R21") (pintype "passive"))
      (node (ref "DD1") (pin "R26") (pinfunction "GND_R26") (pintype "passive"))
      (node (ref "DD1") (pin "T12") (pinfunction "GND_T12") (pintype "passive"))
      (node (ref "DD1") (pin "T13") (pinfunction "GND_T13") (pintype "passive"))
      (node (ref "DD1") (pin "T14") (pinfunction "GND_T14") (pintype "passive"))
      (node (ref "DD1") (pin "T15") (pinfunction "GND_T15") (pintype "passive"))
      (node (ref "DD1") (pin "T5") (pinfunction "GND_T5") (pintype "passive"))
      (node (ref "DD1") (pin "U19") (pinfunction "GND_U19") (pintype "passive"))
      (node (ref "DD1") (pin "U8") (pinfunction "GND_U8") (pintype "passive"))
      (node (ref "DD1") (pin "W13") (pinfunction "GND_W13") (pintype "passive"))
      (node (ref "DD1") (pin "W14") (pinfunction "GND_W14") (pintype "passive"))
      (node (ref "DD1") (pin "W20") (pinfunction "GND_PLL4_W20") (pintype "passive"))
      (node (ref "DD1") (pin "W22") (pinfunction "GND_W22") (pintype "passive"))
      (node (ref "DD1") (pin "W5") (pinfunction "GND_W5") (pintype "passive"))
      (node (ref "DD1") (pin "W7") (pinfunction "GND_PLL1_W7") (pintype "passive"))
      (node (ref "DD1") (pin "Y17") (pinfunction "GND_Y17") (pintype "passive"))
      (node (ref "DD1") (pin "Y19") (pinfunction "GNDA_PLL4_Y19") (pintype "passive"))
      (node (ref "DD1") (pin "Y6") (pinfunction "GND_PLL1_Y6") (pintype "passive"))
      (node (ref "DD1") (pin "Y8") (pinfunction "GNDA_PLL1_Y8") (pintype "passive"))
      (node (ref "DD1") (pin "Y9") (pinfunction "GND_Y9") (pintype "passive"))
    )
  )
)
